# sanguish.net
KiCad netlist of a schematic drawn in EAGLE
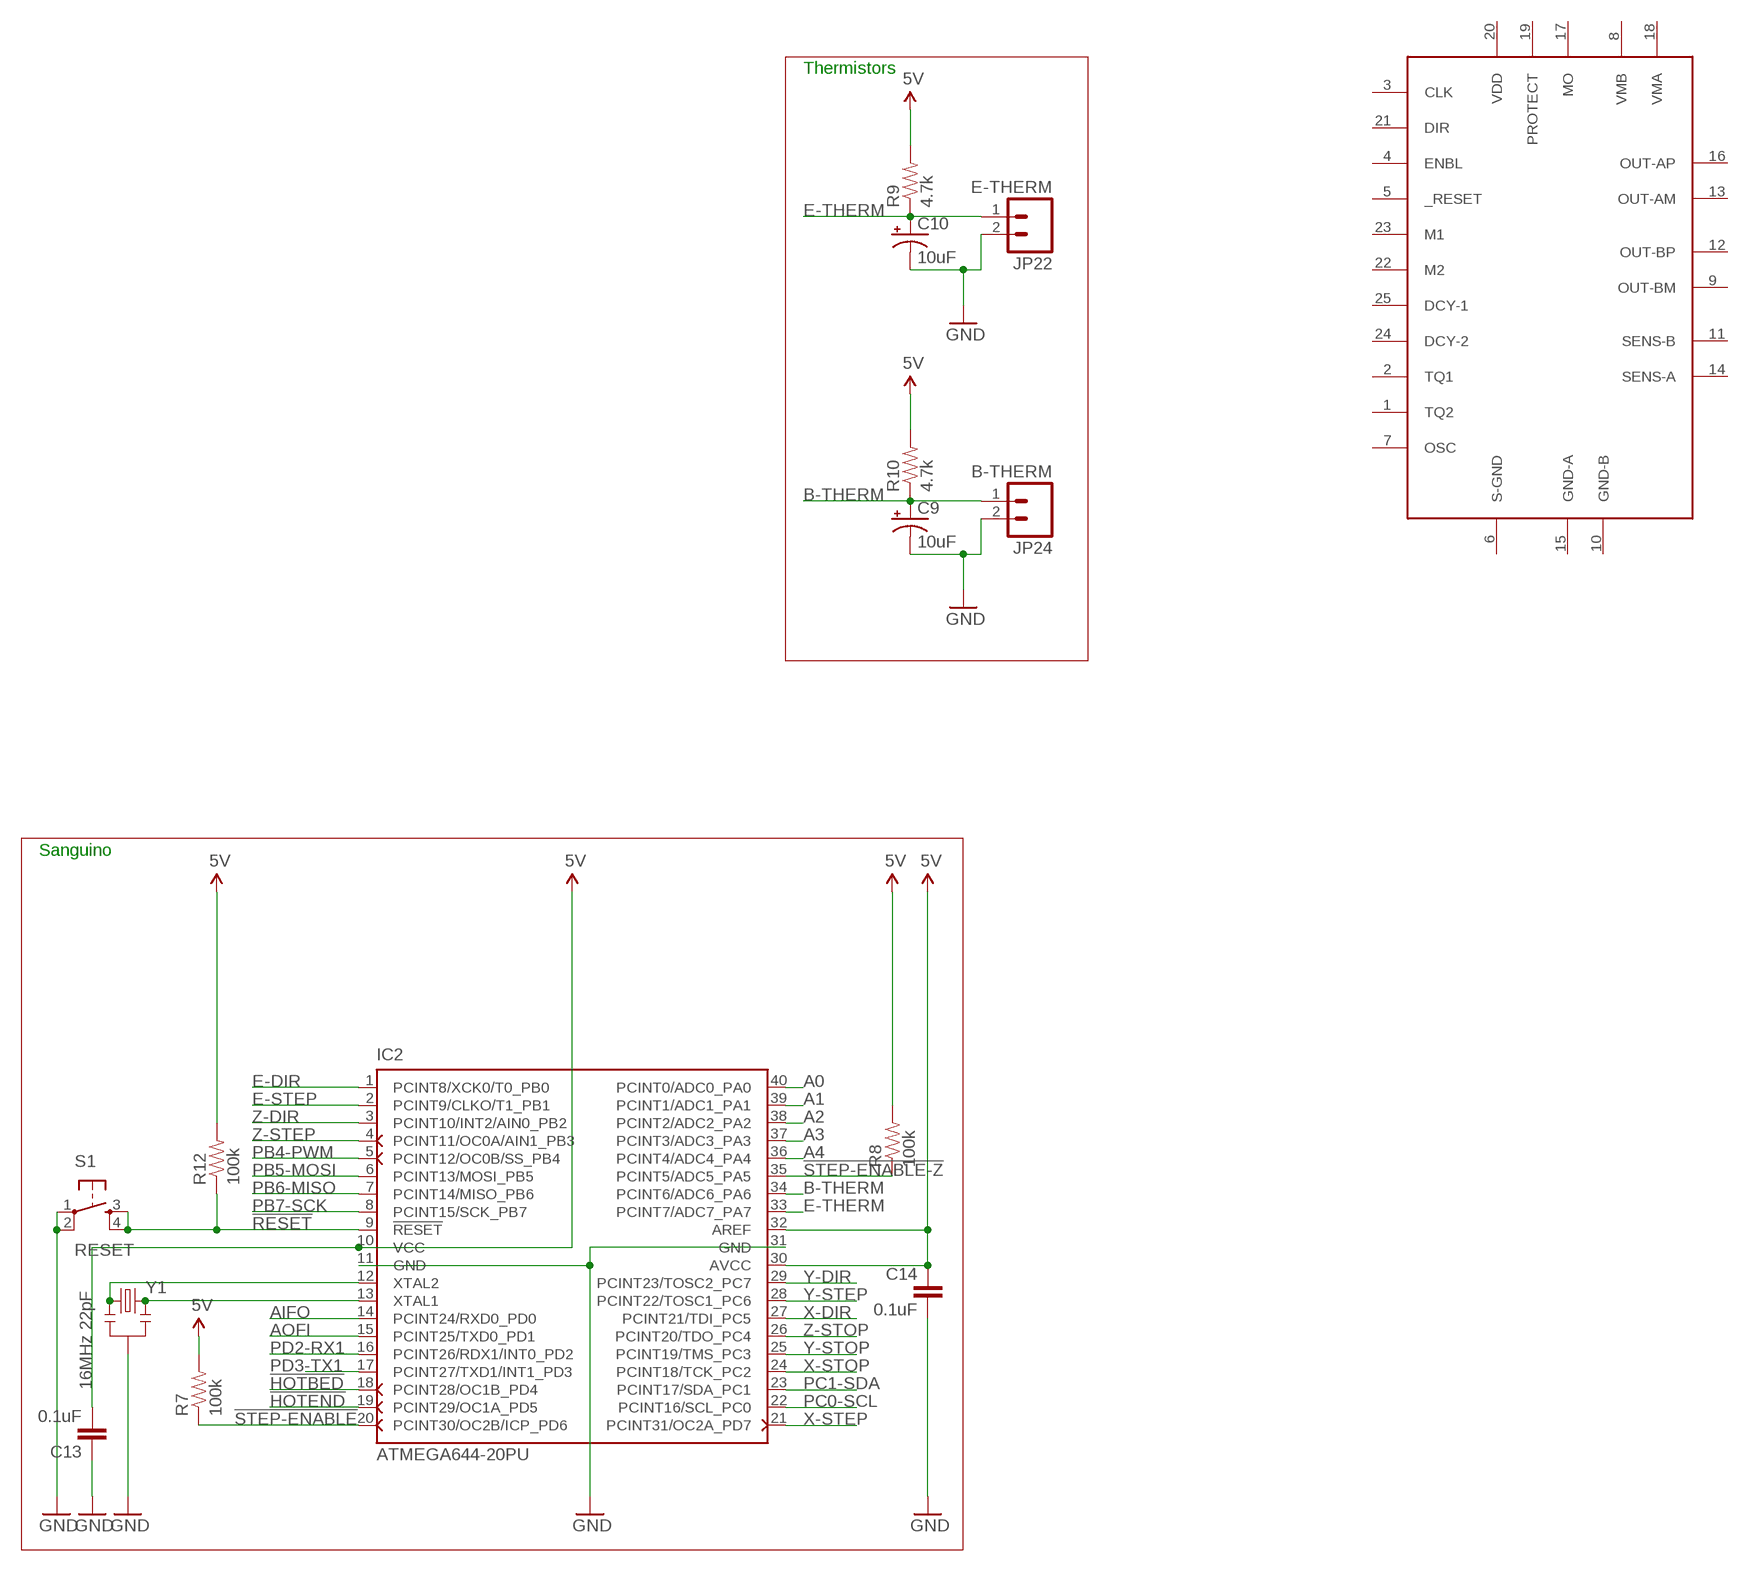
[diagram p0: schematic, sheet 1]

(export (version "E")
  (design (tool "Eeschema 10.0.6"))
  (components
    (comp (ref "C9")
      (value "10uF")
      (footprint "eagle-import:CPOL-RADIAL-10UF-25V")
      (libsource (lib "eagle-import") (part "CAP_POLPTH2"))
    )
    (comp (ref "C10")
      (value "10uF")
      (footprint "eagle-import:CPOL-RADIAL-10UF-25V")
      (libsource (lib "eagle-import") (part "CAP_POLPTH2"))
    )
    (comp (ref "C13")
      (value "0.1uF")
      (footprint "eagle-import:CAP-PTH-SMALL2")
      (libsource (lib "eagle-import") (part "CAPPTH2"))
    )
    (comp (ref "C14")
      (value "0.1uF")
      (footprint "eagle-import:CAP-PTH-SMALL2")
      (libsource (lib "eagle-import") (part "CAPPTH2"))
    )
    (comp (ref "IC2")
      (value "ATMEGA644-20PU")
      (footprint "eagle-import:DIL40")
      (libsource (lib "eagle-import") (part "ATMEGA644-PU20"))
    )
    (comp (ref "JP22")
      (value "E-THERM")
      (footprint "eagle-import:1X02")
      (libsource (lib "eagle-import") (part "M02PTH"))
    )
    (comp (ref "JP24")
      (value "B-THERM")
      (footprint "eagle-import:1X02")
      (libsource (lib "eagle-import") (part "M02PTH"))
    )
    (comp (ref "R7")
      (value "100k")
      (footprint "eagle-import:AXIAL-0.3")
      (libsource (lib "eagle-import") (part "RESISTORPTH1"))
    )
    (comp (ref "R8")
      (value "100k")
      (footprint "eagle-import:AXIAL-0.3")
      (libsource (lib "eagle-import") (part "RESISTORPTH1"))
    )
    (comp (ref "R9")
      (value "4.7k")
      (footprint "eagle-import:AXIAL-0.3")
      (libsource (lib "eagle-import") (part "RESISTORPTH1"))
    )
    (comp (ref "R10")
      (value "4.7k")
      (footprint "eagle-import:AXIAL-0.3")
      (libsource (lib "eagle-import") (part "RESISTORPTH1"))
    )
    (comp (ref "R12")
      (value "100k")
      (footprint "eagle-import:AXIAL-0.3")
      (libsource (lib "eagle-import") (part "RESISTORPTH1"))
    )
    (comp (ref "S1")
      (value "RESET")
      (footprint "eagle-import:TACTILE-PTH")
      (libsource (lib "eagle-import") (part "TAC_SWITCHPTH"))
    )
    (comp (ref "U$1")
      (value "TB6560")
      (footprint "eagle-import:ZIP25")
      (libsource (lib "eagle-import") (part "TB6560"))
    )
    (comp (ref "Y1")
      (value "16MHz 22pF")
      (footprint "eagle-import:RESONATOR-PTH")
      (libsource (lib "eagle-import") (part "RESONATORPTH"))
    )
  )
  (nets
    (net (code "1") (name "/A0") (class "Default")
      (node (ref "IC2") (pin "40") (pinfunction "PCINT0/ADC0_PA0_40") (pintype "bidirectional"))
    )
    (net (code "2") (name "/A1") (class "Default")
      (node (ref "IC2") (pin "39") (pinfunction "PCINT1/ADC1_PA1_39") (pintype "bidirectional"))
    )
    (net (code "3") (name "/A2") (class "Default")
      (node (ref "IC2") (pin "38") (pinfunction "PCINT2/ADC2_PA2_38") (pintype "bidirectional"))
    )
    (net (code "4") (name "/A3") (class "Default")
      (node (ref "IC2") (pin "37") (pinfunction "PCINT3/ADC3_PA3_37") (pintype "bidirectional"))
    )
    (net (code "5") (name "/A4") (class "Default")
      (node (ref "IC2") (pin "36") (pinfunction "PCINT4/ADC4_PA4_36") (pintype "bidirectional"))
    )
    (net (code "6") (name "/AIFO") (class "Default")
      (node (ref "IC2") (pin "14") (pinfunction "PCINT24/RXD0_PD0_14") (pintype "bidirectional"))
    )
    (net (code "7") (name "/AOFI") (class "Default")
      (node (ref "IC2") (pin "15") (pinfunction "PCINT25/TXD0_PD1_15") (pintype "bidirectional"))
    )
    (net (code "8") (name "/B-THERM") (class "Default")
      (node (ref "C9") (pin "1") (pinfunction "+_1") (pintype "passive"))
      (node (ref "IC2") (pin "34") (pinfunction "PCINT6/ADC6_PA6_34") (pintype "bidirectional"))
      (node (ref "JP24") (pin "1") (pinfunction "1_1") (pintype "passive"))
      (node (ref "R10") (pin "P$1") (pinfunction "1_P$1") (pintype "passive"))
    )
    (net (code "9") (name "/E-DIR") (class "Default")
      (node (ref "IC2") (pin "1") (pinfunction "PCINT8/XCK0/T0_PB0_1") (pintype "bidirectional"))
    )
    (net (code "10") (name "/E-STEP") (class "Default")
      (node (ref "IC2") (pin "2") (pinfunction "PCINT9/CLKO/T1_PB1_2") (pintype "bidirectional"))
    )
    (net (code "11") (name "/E-THERM") (class "Default")
      (node (ref "C10") (pin "1") (pinfunction "+_1") (pintype "passive"))
      (node (ref "IC2") (pin "33") (pinfunction "PCINT7/ADC7_PA7_33") (pintype "bidirectional"))
      (node (ref "JP22") (pin "1") (pinfunction "1_1") (pintype "passive"))
      (node (ref "R9") (pin "P$1") (pinfunction "1_P$1") (pintype "passive"))
    )
    (net (code "12") (name "/PB4-PWM") (class "Default")
      (node (ref "IC2") (pin "5") (pinfunction "PCINT12/OC0B/SS_PB4_5") (pintype "bidirectional"))
    )
    (net (code "13") (name "/PB5-MOSI") (class "Default")
      (node (ref "IC2") (pin "6") (pinfunction "PCINT13/MOSI_PB5_6") (pintype "bidirectional"))
    )
    (net (code "14") (name "/PB6-MISO") (class "Default")
      (node (ref "IC2") (pin "7") (pinfunction "PCINT14/MISO_PB6_7") (pintype "bidirectional"))
    )
    (net (code "15") (name "/PB7-SCK") (class "Default")
      (node (ref "IC2") (pin "8") (pinfunction "PCINT15/SCK_PB7_8") (pintype "bidirectional"))
    )
    (net (code "16") (name "/PC0-SCL") (class "Default")
      (node (ref "IC2") (pin "22") (pinfunction "PCINT16/SCL_PC0_22") (pintype "bidirectional"))
    )
    (net (code "17") (name "/PC1-SDA") (class "Default")
      (node (ref "IC2") (pin "23") (pinfunction "PCINT17/SDA_PC1_23") (pintype "bidirectional"))
    )
    (net (code "18") (name "/PD2-RX1") (class "Default")
      (node (ref "IC2") (pin "16") (pinfunction "PCINT26/RDX1/INT0_PD2_16") (pintype "bidirectional"))
    )
    (net (code "19") (name "/PD3-TX1") (class "Default")
      (node (ref "IC2") (pin "17") (pinfunction "PCINT27/TXD1/INT1_PD3_17") (pintype "bidirectional"))
    )
    (net (code "20") (name "/X-DIR") (class "Default")
      (node (ref "IC2") (pin "27") (pinfunction "PCINT21/TDI_PC5_27") (pintype "bidirectional"))
    )
    (net (code "21") (name "/X-STEP") (class "Default")
      (node (ref "IC2") (pin "21") (pinfunction "PCINT31/OC2A_PD7_21") (pintype "bidirectional"))
    )
    (net (code "22") (name "/X-STOP") (class "Default")
      (node (ref "IC2") (pin "24") (pinfunction "PCINT18/TCK_PC2_24") (pintype "bidirectional"))
    )
    (net (code "23") (name "/Y-DIR") (class "Default")
      (node (ref "IC2") (pin "29") (pinfunction "PCINT23/TOSC2_PC7_29") (pintype "bidirectional"))
    )
    (net (code "24") (name "/Y-STEP") (class "Default")
      (node (ref "IC2") (pin "28") (pinfunction "PCINT22/TOSC1_PC6_28") (pintype "bidirectional"))
    )
    (net (code "25") (name "/Y-STOP") (class "Default")
      (node (ref "IC2") (pin "25") (pinfunction "PCINT19/TMS_PC3_25") (pintype "bidirectional"))
    )
    (net (code "26") (name "/Z-DIR") (class "Default")
      (node (ref "IC2") (pin "3") (pinfunction "PCINT10/INT2/AIN0_PB2_3") (pintype "bidirectional"))
    )
    (net (code "27") (name "/Z-STEP") (class "Default")
      (node (ref "IC2") (pin "4") (pinfunction "PCINT11/OC0A/AIN1_PB3_4") (pintype "bidirectional"))
    )
    (net (code "28") (name "/Z-STOP") (class "Default")
      (node (ref "IC2") (pin "26") (pinfunction "PCINT20/TDO_PC4_26") (pintype "bidirectional"))
    )
    (net (code "29") (name "/~{HOTBED}") (class "Default")
      (node (ref "IC2") (pin "18") (pinfunction "PCINT28/OC1B_PD4_18") (pintype "bidirectional"))
    )
    (net (code "30") (name "/~{HOTEND}") (class "Default")
      (node (ref "IC2") (pin "19") (pinfunction "PCINT29/OC1A_PD5_19") (pintype "bidirectional"))
    )
    (net (code "31") (name "/~{RESET}") (class "Default")
      (node (ref "IC2") (pin "9") (pinfunction "~{RESET}_9") (pintype "input"))
      (node (ref "R12") (pin "P$1") (pinfunction "1_P$1") (pintype "passive"))
      (node (ref "S1") (pin "3") (pinfunction "3_3") (pintype "passive"))
      (node (ref "S1") (pin "4") (pinfunction "4_4") (pintype "passive"))
    )
    (net (code "32") (name "/~{STEP-ENABLE-Z}") (class "Default")
      (node (ref "IC2") (pin "35") (pinfunction "PCINT5/ADC5_PA5_35") (pintype "bidirectional"))
      (node (ref "R8") (pin "P$1") (pinfunction "1_P$1") (pintype "passive"))
    )
    (net (code "33") (name "/~{STEP-ENABLE}") (class "Default")
      (node (ref "IC2") (pin "20") (pinfunction "PCINT30/OC2B/ICP_PD6_20") (pintype "bidirectional"))
      (node (ref "R7") (pin "P$1") (pinfunction "1_P$1") (pintype "passive"))
    )
    (net (code "34") (name "5V") (class "Default")
      (node (ref "C13") (pin "2") (pinfunction "2_2") (pintype "passive"))
      (node (ref "C14") (pin "1") (pinfunction "1_1") (pintype "passive"))
      (node (ref "IC2") (pin "10") (pinfunction "VCC_10") (pintype "power_in"))
      (node (ref "IC2") (pin "30") (pinfunction "AVCC_30") (pintype "power_in"))
      (node (ref "IC2") (pin "32") (pinfunction "AREF_32") (pintype "passive"))
      (node (ref "R10") (pin "P$2") (pinfunction "2_P$2") (pintype "passive"))
      (node (ref "R12") (pin "P$2") (pinfunction "2_P$2") (pintype "passive"))
      (node (ref "R7") (pin "P$2") (pinfunction "2_P$2") (pintype "passive"))
      (node (ref "R8") (pin "P$2") (pinfunction "2_P$2") (pintype "passive"))
      (node (ref "R9") (pin "P$2") (pinfunction "2_P$2") (pintype "passive"))
    )
    (net (code "35") (name "GND") (class "Default")
      (node (ref "C10") (pin "2") (pinfunction "-_2") (pintype "passive"))
      (node (ref "C13") (pin "1") (pinfunction "1_1") (pintype "passive"))
      (node (ref "C14") (pin "2") (pinfunction "2_2") (pintype "passive"))
      (node (ref "C9") (pin "2") (pinfunction "-_2") (pintype "passive"))
      (node (ref "IC2") (pin "11") (pinfunction "GND_11") (pintype "power_in"))
      (node (ref "IC2") (pin "31") (pinfunction "GND_31") (pintype "power_in"))
      (node (ref "JP22") (pin "2") (pinfunction "2_2") (pintype "passive"))
      (node (ref "JP24") (pin "2") (pinfunction "2_2") (pintype "passive"))
      (node (ref "S1") (pin "1") (pinfunction "1_1") (pintype "passive"))
      (node (ref "S1") (pin "2") (pinfunction "2_2") (pintype "passive"))
      (node (ref "Y1") (pin "2") (pinfunction "2_2") (pintype "passive"))
    )
    (net (code "36") (name "Net-(IC2-XTAL1)") (class "Default")
      (node (ref "IC2") (pin "13") (pinfunction "XTAL1_13") (pintype "input"))
      (node (ref "Y1") (pin "3") (pinfunction "3_3") (pintype "passive"))
    )
    (net (code "37") (name "Net-(IC2-XTAL2)") (class "Default")
      (node (ref "IC2") (pin "12") (pinfunction "XTAL2_12") (pintype "output"))
      (node (ref "Y1") (pin "1") (pinfunction "1_1") (pintype "passive"))
    )
    (net (code "38") (name "unconnected-(U$1-CLK-Pad3)") (class "Default")
      (node (ref "U$1") (pin "3") (pinfunction "CLK_3") (pintype "bidirectional"))
    )
    (net (code "39") (name "unconnected-(U$1-DCY-1-Pad25)") (class "Default")
      (node (ref "U$1") (pin "25") (pinfunction "DCY-1_25") (pintype "bidirectional"))
    )
    (net (code "40") (name "unconnected-(U$1-DCY-2-Pad24)") (class "Default")
      (node (ref "U$1") (pin "24") (pinfunction "DCY-2_24") (pintype "bidirectional"))
    )
    (net (code "41") (name "unconnected-(U$1-DIR-Pad21)") (class "Default")
      (node (ref "U$1") (pin "21") (pinfunction "DIR_21") (pintype "bidirectional"))
    )
    (net (code "42") (name "unconnected-(U$1-ENBL-Pad4)") (class "Default")
      (node (ref "U$1") (pin "4") (pinfunction "ENBL_4") (pintype "bidirectional"))
    )
    (net (code "43") (name "unconnected-(U$1-GND-A-Pad15)") (class "Default")
      (node (ref "U$1") (pin "15") (pinfunction "GND-A_15") (pintype "bidirectional"))
    )
    (net (code "44") (name "unconnected-(U$1-GND-B-Pad10)") (class "Default")
      (node (ref "U$1") (pin "10") (pinfunction "GND-B_10") (pintype "bidirectional"))
    )
    (net (code "45") (name "unconnected-(U$1-M1-Pad23)") (class "Default")
      (node (ref "U$1") (pin "23") (pinfunction "M1_23") (pintype "bidirectional"))
    )
    (net (code "46") (name "unconnected-(U$1-M2-Pad22)") (class "Default")
      (node (ref "U$1") (pin "22") (pinfunction "M2_22") (pintype "bidirectional"))
    )
    (net (code "47") (name "unconnected-(U$1-MO-Pad17)") (class "Default")
      (node (ref "U$1") (pin "17") (pinfunction "MO_17") (pintype "bidirectional"))
    )
    (net (code "48") (name "unconnected-(U$1-OSC-Pad7)") (class "Default")
      (node (ref "U$1") (pin "7") (pinfunction "OSC_7") (pintype "bidirectional"))
    )
    (net (code "49") (name "unconnected-(U$1-OUT-AM-Pad13)") (class "Default")
      (node (ref "U$1") (pin "13") (pinfunction "OUT-AM_13") (pintype "output"))
    )
    (net (code "50") (name "unconnected-(U$1-OUT-AP-Pad16)") (class "Default")
      (node (ref "U$1") (pin "16") (pinfunction "OUT-AP_16") (pintype "output"))
    )
    (net (code "51") (name "unconnected-(U$1-OUT-BM-Pad9)") (class "Default")
      (node (ref "U$1") (pin "9") (pinfunction "OUT-BM_9") (pintype "output"))
    )
    (net (code "52") (name "unconnected-(U$1-OUT-BP-Pad12)") (class "Default")
      (node (ref "U$1") (pin "12") (pinfunction "OUT-BP_12") (pintype "output"))
    )
    (net (code "53") (name "unconnected-(U$1-PROTECT-Pad19)") (class "Default")
      (node (ref "U$1") (pin "19") (pinfunction "PROTECT_19") (pintype "bidirectional"))
    )
    (net (code "54") (name "unconnected-(U$1-S-GND-Pad6)") (class "Default")
      (node (ref "U$1") (pin "6") (pinfunction "S-GND_6") (pintype "bidirectional"))
    )
    (net (code "55") (name "unconnected-(U$1-SENS-A-Pad14)") (class "Default")
      (node (ref "U$1") (pin "14") (pinfunction "SENS-A_14") (pintype "bidirectional"))
    )
    (net (code "56") (name "unconnected-(U$1-SENS-B-Pad11)") (class "Default")
      (node (ref "U$1") (pin "11") (pinfunction "SENS-B_11") (pintype "bidirectional"))
    )
    (net (code "57") (name "unconnected-(U$1-TQ1-Pad2)") (class "Default")
      (node (ref "U$1") (pin "2") (pinfunction "TQ1_2") (pintype "bidirectional"))
    )
    (net (code "58") (name "unconnected-(U$1-TQ2-Pad1)") (class "Default")
      (node (ref "U$1") (pin "1") (pinfunction "TQ2_1") (pintype "bidirectional"))
    )
    (net (code "59") (name "unconnected-(U$1-VDD-Pad20)") (class "Default")
      (node (ref "U$1") (pin "20") (pinfunction "VDD_20") (pintype "bidirectional"))
    )
    (net (code "60") (name "unconnected-(U$1-VMA-Pad18)") (class "Default")
      (node (ref "U$1") (pin "18") (pinfunction "VMA_18") (pintype "bidirectional"))
    )
    (net (code "61") (name "unconnected-(U$1-VMB-Pad8)") (class "Default")
      (node (ref "U$1") (pin "8") (pinfunction "VMB_8") (pintype "bidirectional"))
    )
    (net (code "62") (name "unconnected-(U$1-_RESET-Pad5)") (class "Default")
      (node (ref "U$1") (pin "5") (pinfunction "_RESET_5") (pintype "bidirectional"))
    )
  )
)
